# highAmpLedStrip.net
KiCad netlist of a schematic drawn in EAGLE
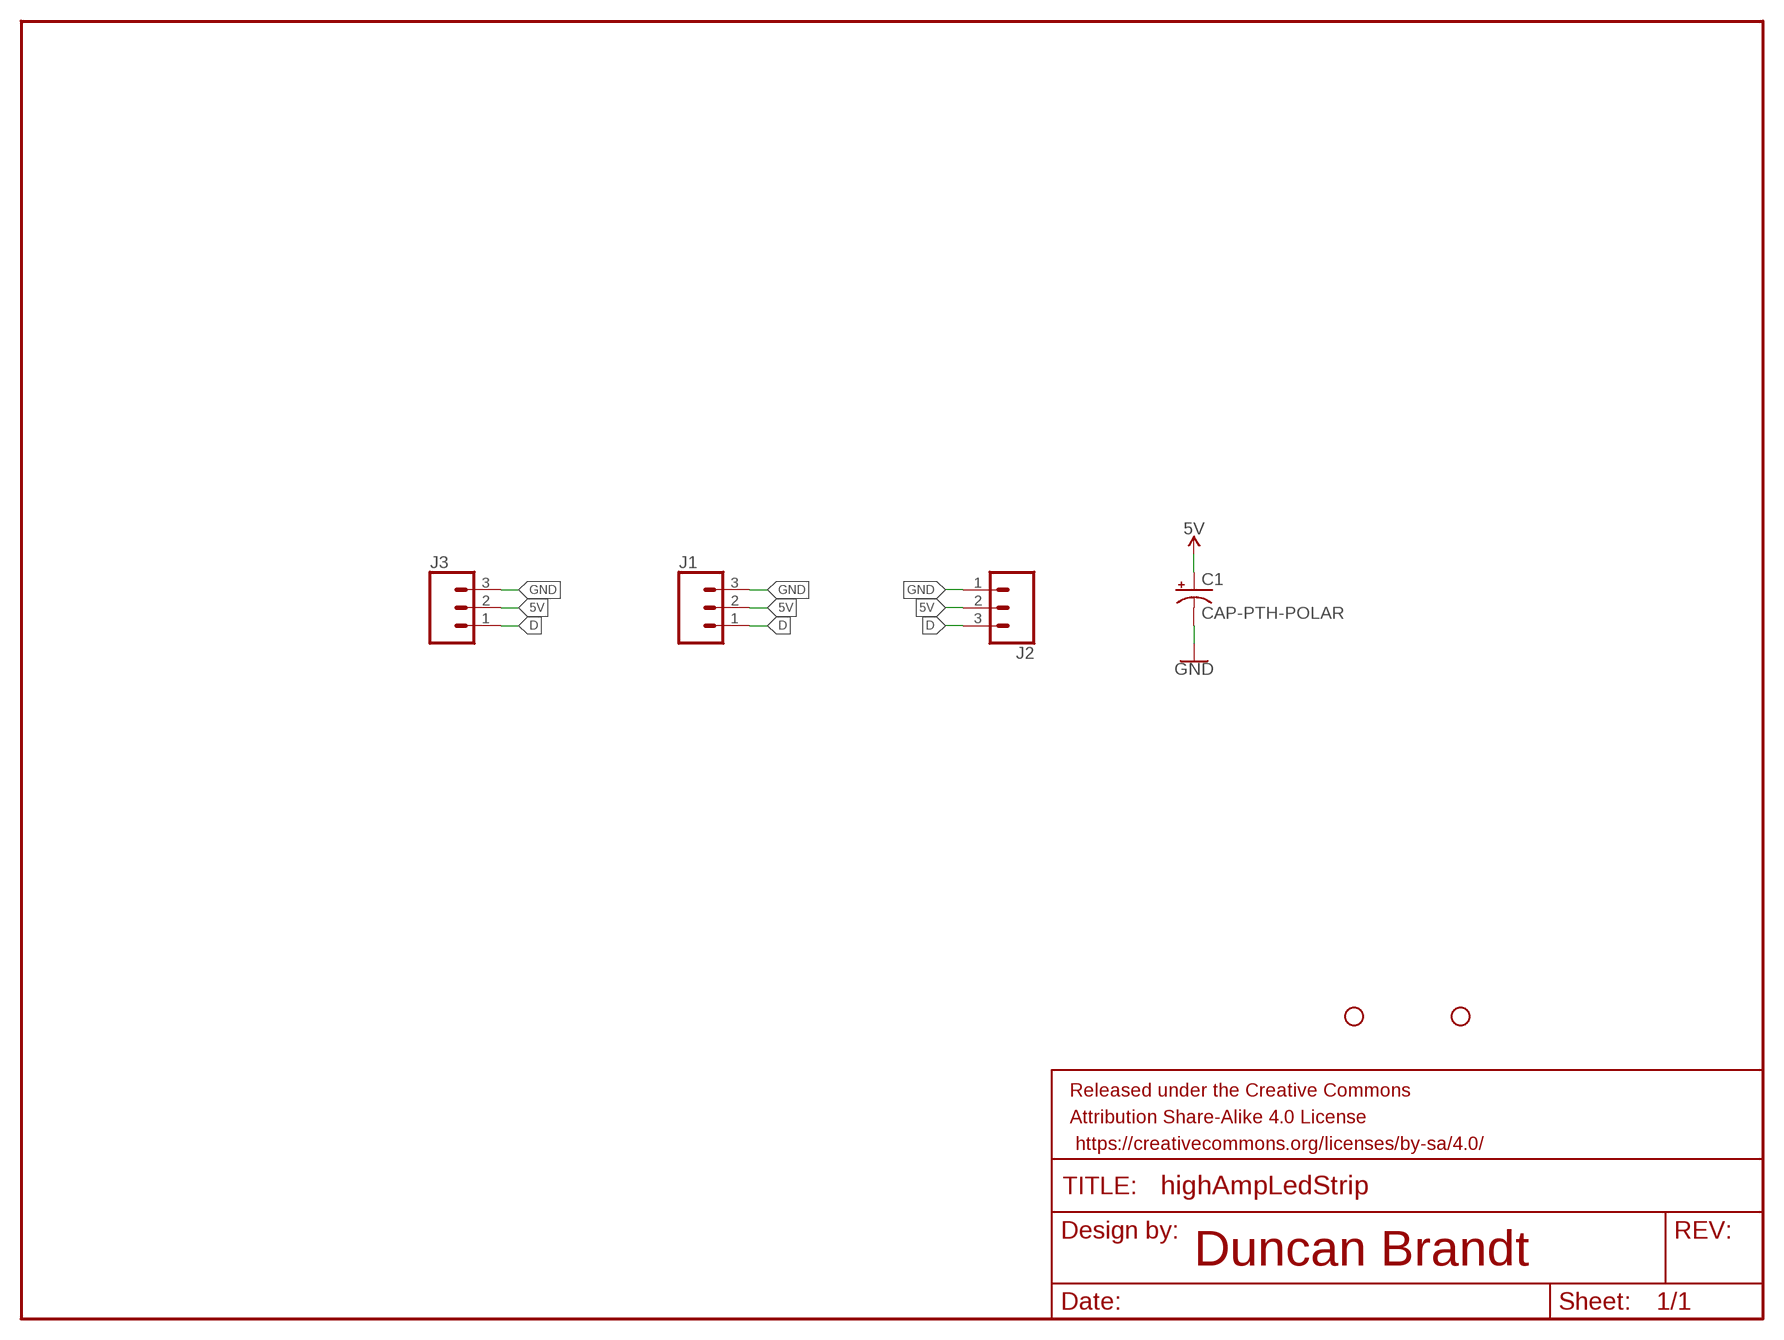
[diagram p0: schematic, sheet 1]

(export (version "E")
  (design (tool "Eeschema 10.0.6"))
  (components
    (comp (ref "C1")
      (value "CAP-PTH-POLAR")
      (footprint "eagle-import:CPOL-RADIAL-2.5MM-5MM")
      (libsource (lib "eagle-import") (part "CAP-PTH-POLAR"))
    )
    (comp (ref "FRAME1")
      (value "FRAME-LETTER")
      (footprint "eagle-import:CREATIVE_COMMONS")
      (libsource (lib "eagle-import") (part "FRAME-LETTER"))
    )
    (comp (ref "H1")
      (value "STAND-OFF")
      (footprint "eagle-import:STAND-OFF")
      (libsource (lib "eagle-import") (part "STAND-OFF"))
    )
    (comp (ref "H2")
      (value "STAND-OFF")
      (footprint "eagle-import:STAND-OFF")
      (libsource (lib "eagle-import") (part "STAND-OFF"))
    )
    (comp (ref "J1")
      (value "CONN_03LONGPADS")
      (footprint "eagle-import:1X03_LEDSTRIP_LONGPADS")
      (libsource (lib "eagle-import") (part "CONN_03LONGPADS"))
    )
    (comp (ref "J2")
      (value "CONN_031X03_NO_SILK")
      (footprint "eagle-import:1X03_5MM_SCREWTERM")
      (libsource (lib "eagle-import") (part "CONN_031X03_NO_SILK"))
    )
    (comp (ref "J3")
      (value "CONN_03")
      (footprint "eagle-import:1X03")
      (libsource (lib "eagle-import") (part "CONN_03"))
    )
  )
  (nets
    (net (code "1") (name "5V") (class "Default")
      (node (ref "C1") (pin "1") (pinfunction "+_1") (pintype "passive"))
      (node (ref "J1") (pin "2") (pinfunction "2_2") (pintype "passive"))
      (node (ref "J2") (pin "2") (pinfunction "2_2") (pintype "passive"))
      (node (ref "J3") (pin "2") (pinfunction "2_2") (pintype "passive"))
    )
    (net (code "2") (name "D") (class "Default")
      (node (ref "J1") (pin "1") (pinfunction "1_1") (pintype "passive"))
      (node (ref "J2") (pin "3") (pinfunction "3_3") (pintype "passive"))
      (node (ref "J3") (pin "1") (pinfunction "1_1") (pintype "passive"))
    )
    (net (code "3") (name "GND") (class "Default")
      (node (ref "C1") (pin "2") (pinfunction "-_2") (pintype "passive"))
      (node (ref "J1") (pin "3") (pinfunction "3_3") (pintype "passive"))
      (node (ref "J2") (pin "1") (pinfunction "1_1") (pintype "passive"))
      (node (ref "J3") (pin "3") (pinfunction "3_3") (pintype "passive"))
    )
  )
)
